# USB-IRIS-W1_INTERFACE.net
KiCad netlist of a schematic drawn in Altium Designer
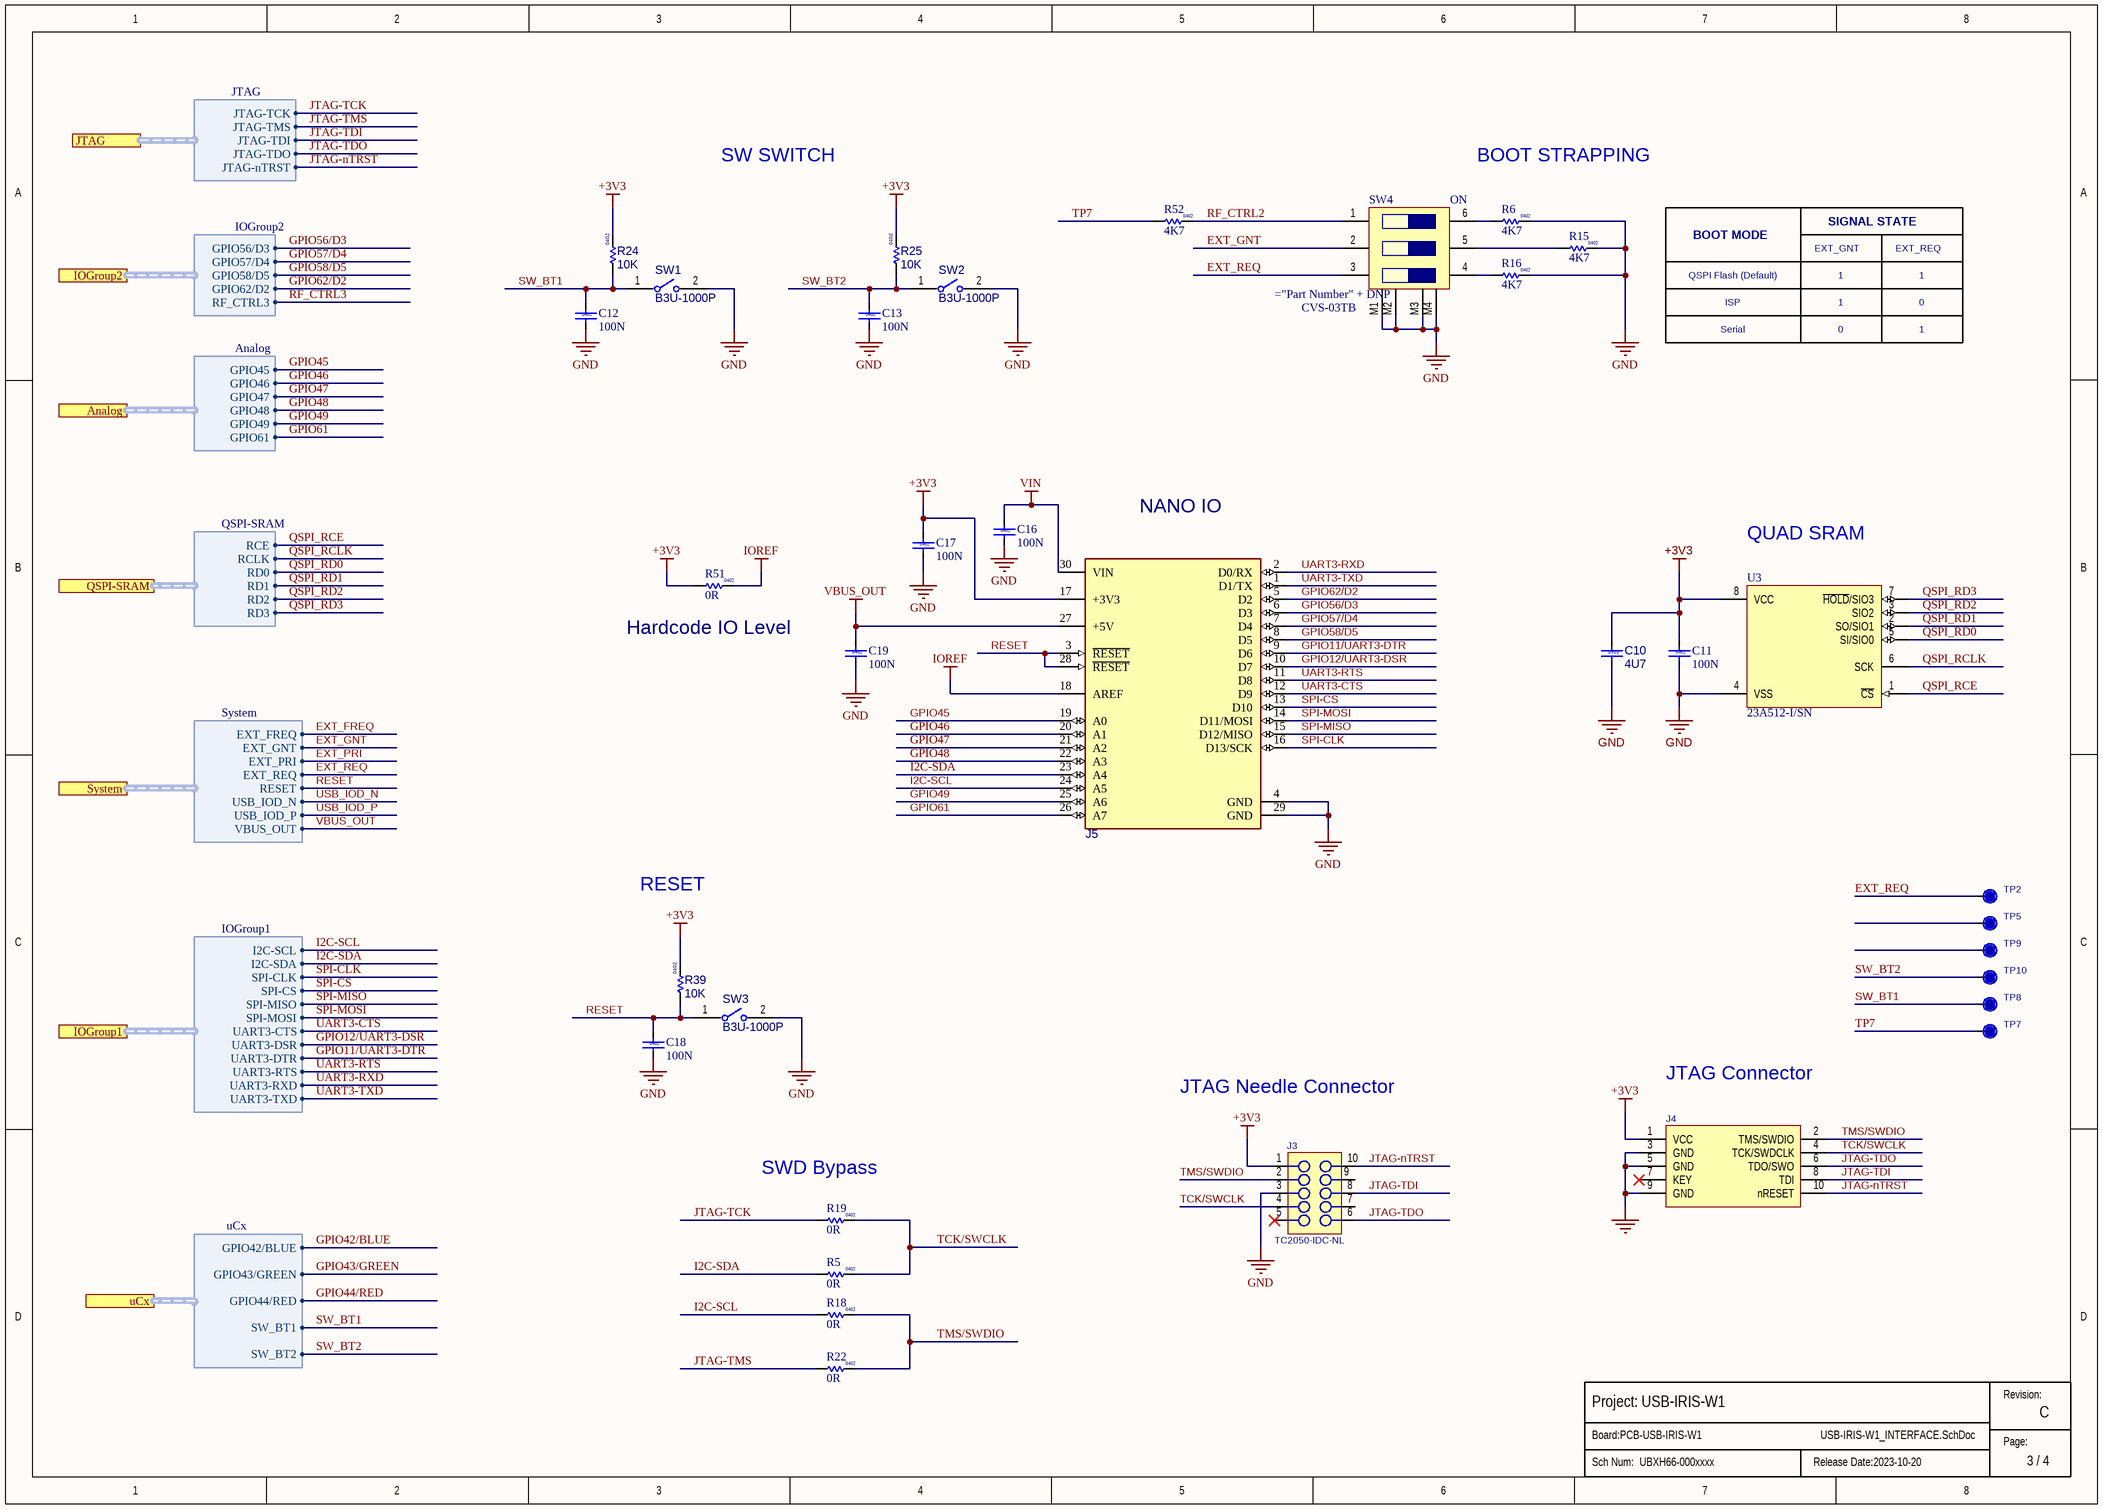
[diagram p0: USB-IRIS-W1_INTERFACE.SchDoc]

(export (version "E")
  (design (tool "Eeschema 10.0.6"))
  (components
    (comp (ref "C10")
      (value "4U7")
      (footprint "Cap 0402 HD")
      (description "CAP CER X5R 0402")
      (fields
        (field (name "SIZE") "0x0y")
        (field (name "PART NUMBER") "UBXH01-0000243")
        (field (name "TOLERANCE") "20%")
        (field (name "EDITOR") "dario.antonaz")
        (field (name "RELEASED BY") "pasquale.scorca")
      )
      (libsource (lib "UBX_Parts_DB_Lib") (part "Cap Chip"))
    )
    (comp (ref "C11")
      (value "100N")
      (footprint "Cap 0402 HD")
      (description "CAP CER X5R 0402 100N 10% 10V")
      (fields
        (field (name "SIZE") "0402")
        (field (name "PART NUMBER") "UBXH01-2021002")
        (field (name "TOLERANCE") "10%")
        (field (name "EDITOR") "roland.rust")
        (field (name "RELEASED BY") "roland.rust")
      )
      (libsource (lib "UBX_Parts_DB_Lib") (part "Cap Chip"))
    )
    (comp (ref "C12")
      (value "100N")
      (footprint "Cap 0402")
      (description "CAP CER X5R 0402 100N 10% 10V")
      (fields
        (field (name "SIZE") "0402")
        (field (name "PART NUMBER") "UBXH01-2021002")
        (field (name "TOLERANCE") "10%")
        (field (name "EDITOR") "roland.rust")
        (field (name "RELEASED BY") "roland.rust")
      )
      (libsource (lib "UBX_Parts_DB_Lib") (part "Cap Chip"))
    )
    (comp (ref "C13")
      (value "100N")
      (footprint "Cap 0402")
      (description "CAP CER X5R 0402 100N 10% 10V")
      (fields
        (field (name "SIZE") "0402")
        (field (name "PART NUMBER") "UBXH01-2021002")
        (field (name "TOLERANCE") "10%")
        (field (name "EDITOR") "roland.rust")
        (field (name "RELEASED BY") "roland.rust")
      )
      (libsource (lib "UBX_Parts_DB_Lib") (part "Cap Chip"))
    )
    (comp (ref "C16")
      (value "100N")
      (footprint "Cap 0402 HD")
      (description "CAP CER X5R 0402 100N 10% 10V")
      (fields
        (field (name "SIZE") "0402")
        (field (name "PART NUMBER") "UBXH01-2021002")
        (field (name "TOLERANCE") "10%")
        (field (name "EDITOR") "roland.rust")
        (field (name "RELEASED BY") "roland.rust")
      )
      (libsource (lib "UBX_Parts_DB_Lib") (part "Cap Chip"))
    )
    (comp (ref "C17")
      (value "100N")
      (footprint "Cap 0402 HD")
      (description "CAP CER X5R 0402 100N 10% 10V")
      (fields
        (field (name "SIZE") "0402")
        (field (name "PART NUMBER") "UBXH01-2021002")
        (field (name "TOLERANCE") "10%")
        (field (name "EDITOR") "roland.rust")
        (field (name "RELEASED BY") "roland.rust")
      )
      (libsource (lib "UBX_Parts_DB_Lib") (part "Cap Chip"))
    )
    (comp (ref "C18")
      (value "100N")
      (footprint "Cap 0402")
      (description "CAP CER X5R 0402 100N 10% 10V")
      (fields
        (field (name "SIZE") "0402")
        (field (name "PART NUMBER") "UBXH01-2021002")
        (field (name "TOLERANCE") "10%")
        (field (name "EDITOR") "roland.rust")
        (field (name "RELEASED BY") "roland.rust")
      )
      (libsource (lib "UBX_Parts_DB_Lib") (part "Cap Chip"))
    )
    (comp (ref "C19")
      (value "100N")
      (footprint "Cap 0402 HD")
      (description "CAP CER X5R 0402 100N 10% 10V")
      (fields
        (field (name "SIZE") "0402")
        (field (name "PART NUMBER") "UBXH01-2021002")
        (field (name "TOLERANCE") "10%")
        (field (name "EDITOR") "roland.rust")
        (field (name "RELEASED BY") "roland.rust")
      )
      (libsource (lib "UBX_Parts_DB_Lib") (part "Cap Chip"))
    )
    (comp (ref "J3")
      (value "TC2050-IDC-NLDNP")
      (footprint "TC2050-IDC-NL")
      (description "CON PADS FOR CBL PLUG-OF-NAILS 10-PIN NO LEGS")
      (fields
        (field (name "MANUFACTURER P/N") "TC2050-IDC-NL")
        (field (name "PART NUMBER") "TC2050-IDC-NL")
        (field (name "MANUFACTURER") "TAG Connect")
        (field (name "ADDED BY") "Paul B")
      )
      (libsource (lib "LEGACY_Rigado_AltiumLib") (part "CON-10Pin_2Row_ALT"))
    )
    (comp (ref "J4")
      (value "130-00099")
      (footprint "HDR.050P-10Pin-2x5-SMT_Key")
      (description "Header 0.05\" 10Pin 2Row SMD Black")
      (fields (field (name "MANUFACTURER") "Samtec"))
      (libsource (lib "Arena_Parts_DB_Lib") (part "JTAG-10Pin"))
    )
    (comp (ref "J5")
      (value "UNK_Arduino")
      (footprint "UNK_Arduino")
      (description "ARDUINO NANO 33 IOT CONN")
      (fields (field (name "PART NUMBER") "UBXH04-0000717") (field (name "EDITOR") "aneeb.sohail"))
      (libsource (lib "UBX_Parts_DB_Lib") (part "UNK_Arduino"))
    )
    (comp (ref "R5")
      (value "0R")
      (footprint "RES_0402_1100Lx600Wx400H_500x600Pad_400G_FLX")
      (description "RES THICK FILM CHIP 0402 0R 0 100mW")
      (fields
        (field (name "SIZE") "0402")
        (field (name "PART NUMBER") "UBXH18-0003002")
        (field (name "TOLERANCE") "0")
        (field (name "EDITOR") "charlotte.biber")
        (field (name "RELEASED BY") "peter.mueller")
      )
      (libsource (lib "UBX_Parts_DB_Lib") (part "Res sm"))
    )
    (comp (ref "R6")
      (value "4K7")
      (footprint "RES_0402_1100Lx600Wx400H_500x600Pad_400G_FLX")
      (description "RES THICK FILM CHIP 0402 4K7 5% 100mW")
      (fields
        (field (name "SIZE") "0402")
        (field (name "PART NUMBER") "UBXH18-0008065")
        (field (name "TOLERANCE") "5%")
        (field (name "EDITOR") "martin.frauchiger")
        (field (name "RELEASED BY") "martin.frauchiger")
      )
      (libsource (lib "UBX_Parts_DB_Lib") (part "Res sm"))
    )
    (comp (ref "R15")
      (value "4K7")
      (footprint "RES_0402_1100Lx600Wx400H_500x600Pad_400G_FLX")
      (description "RES THICK FILM CHIP 0402 4K7 5% 100mW")
      (fields
        (field (name "SIZE") "0402")
        (field (name "PART NUMBER") "UBXH18-0008065")
        (field (name "TOLERANCE") "5%")
        (field (name "EDITOR") "martin.frauchiger")
        (field (name "RELEASED BY") "martin.frauchiger")
      )
      (libsource (lib "UBX_Parts_DB_Lib") (part "Res sm"))
    )
    (comp (ref "R16")
      (value "4K7")
      (footprint "RES_0402_1100Lx600Wx400H_500x600Pad_400G_FLX")
      (description "RES THICK FILM CHIP 0402 4K7 5% 100mW")
      (fields
        (field (name "SIZE") "0402")
        (field (name "PART NUMBER") "UBXH18-0008065")
        (field (name "TOLERANCE") "5%")
        (field (name "EDITOR") "martin.frauchiger")
        (field (name "RELEASED BY") "martin.frauchiger")
      )
      (libsource (lib "UBX_Parts_DB_Lib") (part "Res sm"))
    )
    (comp (ref "R18")
      (value "0R")
      (footprint "RES_0402_1100Lx600Wx400H_500x600Pad_400G_FLX")
      (description "RES THICK FILM CHIP 0402 0R 0 100mW")
      (fields
        (field (name "SIZE") "0402")
        (field (name "PART NUMBER") "UBXH18-0003002")
        (field (name "TOLERANCE") "0")
        (field (name "EDITOR") "charlotte.biber")
        (field (name "RELEASED BY") "peter.mueller")
      )
      (libsource (lib "UBX_Parts_DB_Lib") (part "Res sm"))
    )
    (comp (ref "R19")
      (value "0R")
      (footprint "RES_0402_1100Lx600Wx400H_500x600Pad_400G_FLX")
      (description "RES THICK FILM CHIP 0402 0R 0 100mW")
      (fields
        (field (name "SIZE") "0402")
        (field (name "PART NUMBER") "UBXH18-0003002")
        (field (name "TOLERANCE") "0")
        (field (name "EDITOR") "charlotte.biber")
        (field (name "RELEASED BY") "peter.mueller")
      )
      (libsource (lib "UBX_Parts_DB_Lib") (part "Res sm"))
    )
    (comp (ref "R22")
      (value "0R")
      (footprint "RES_0402_1100Lx600Wx400H_500x600Pad_400G_FLX")
      (description "RES THICK FILM CHIP 0402 0R 0 100mW")
      (fields
        (field (name "SIZE") "0402")
        (field (name "PART NUMBER") "UBXH18-0003002")
        (field (name "TOLERANCE") "0")
        (field (name "EDITOR") "charlotte.biber")
        (field (name "RELEASED BY") "peter.mueller")
      )
      (libsource (lib "UBX_Parts_DB_Lib") (part "Res sm"))
    )
    (comp (ref "R24")
      (value "10K")
      (footprint "RES 0402 HD")
      (description "RES THICK FILM CHIP 0402 10K 5% 100mW")
      (fields
        (field (name "SIZE") "0402")
        (field (name "PART NUMBER") "UBXH18-0008073")
        (field (name "TOLERANCE") "5%")
        (field (name "EDITOR") "martin.frauchiger")
        (field (name "RELEASED BY") "martin.frauchiger")
      )
      (libsource (lib "UBX_Parts_DB_Lib") (part "Res sm"))
    )
    (comp (ref "R25")
      (value "10K")
      (footprint "RES 0402 HD")
      (description "RES THICK FILM CHIP 0402 10K 5% 100mW")
      (fields
        (field (name "SIZE") "0402")
        (field (name "PART NUMBER") "UBXH18-0008073")
        (field (name "TOLERANCE") "5%")
        (field (name "EDITOR") "martin.frauchiger")
        (field (name "RELEASED BY") "martin.frauchiger")
      )
      (libsource (lib "UBX_Parts_DB_Lib") (part "Res sm"))
    )
    (comp (ref "R39")
      (value "10K")
      (footprint "RES 0402 HD")
      (description "RES THICK FILM CHIP 0402 10K 5% 100mW")
      (fields
        (field (name "SIZE") "0402")
        (field (name "PART NUMBER") "UBXH18-0008073")
        (field (name "TOLERANCE") "5%")
        (field (name "EDITOR") "martin.frauchiger")
        (field (name "RELEASED BY") "martin.frauchiger")
      )
      (libsource (lib "UBX_Parts_DB_Lib") (part "Res sm"))
    )
    (comp (ref "R51")
      (value "0R")
      (footprint "RES_0402_1100Lx600Wx400H_500x600Pad_400G_FLX")
      (description "RES THICK FILM CHIP 0402 0R 0 100mW")
      (fields
        (field (name "SIZE") "0402")
        (field (name "PART NUMBER") "UBXH18-0003002")
        (field (name "TOLERANCE") "0")
        (field (name "EDITOR") "charlotte.biber")
        (field (name "RELEASED BY") "peter.mueller")
      )
      (libsource (lib "UBX_Parts_DB_Lib") (part "Res sm"))
    )
    (comp (ref "R52")
      (value "4K7")
      (footprint "RES_0402_1100Lx600Wx400H_500x600Pad_400G_FLX")
      (description "RES THICK FILM CHIP 0402 4K7 5% 100mW")
      (fields
        (field (name "SIZE") "0402")
        (field (name "PART NUMBER") "UBXH18-0008065")
        (field (name "TOLERANCE") "5%")
        (field (name "EDITOR") "martin.frauchiger")
        (field (name "RELEASED BY") "martin.frauchiger")
      )
      (libsource (lib "UBX_Parts_DB_Lib") (part "Res sm"))
    )
    (comp (ref "SW1")
      (value "B3U-1000P")
      (footprint "FP-B3U-1000P-MFG")
      (description "SWITCH TACTILE SPST-NO 0.05A 12V")
      (libsource (lib "Altium Content Vault") (part "ae622034201233ca1abcedc05908f33"))
    )
    (comp (ref "SW2")
      (value "B3U-1000P")
      (footprint "FP-B3U-1000P-MFG")
      (description "SWITCH TACTILE SPST-NO 0.05A 12V")
      (libsource (lib "Altium Content Vault") (part "ae622034201233ca1abcedc05908f33"))
    )
    (comp (ref "SW3")
      (value "B3U-1000P")
      (footprint "FP-B3U-1000P-MFG")
      (description "SWITCH TACTILE SPST-NO 0.05A 12V")
      (libsource (lib "Altium Content Vault") (part "ae622034201233ca1abcedc05908f33"))
    )
    (comp (ref "SW4")
      (value "UBXH19-0000036")
      (footprint "CVS-03")
      (description "Dip Switch SPST 3 Position Surface Mount Slide (Standard) Actuator 100mA 6VDC")
      (fields (field (name "VOLTAGE") "6V") (field (name "MANUFACTURER PART NUMBER 1") "CVS-03TB"))
      (libsource (lib "Schlib1") (part "CVS-03TB"))
    )
    (comp (ref "TP2")
      (value "TP")
      (footprint "TP10R")
      (description "Testpoint, Round 1.0mm Dia")
      (fields
        (field (name "PART NUMBER") "TP10R")
        (field (name "ADDED BY") "Jeremy D")
        (field (name "CHECKED BY") "Paul B")
      )
      (libsource (lib "LEGACY_Rigado_AltiumLib") (part "TP_R"))
    )
    (comp (ref "TP5")
      (value "TP")
      (footprint "TP10R")
      (description "Testpoint, Round 1.0mm Dia")
      (fields
        (field (name "PART NUMBER") "TP10R")
        (field (name "ADDED BY") "Jeremy D")
        (field (name "CHECKED BY") "Paul B")
      )
      (libsource (lib "LEGACY_Rigado_AltiumLib") (part "TP_R"))
    )
    (comp (ref "TP7")
      (value "TP")
      (footprint "TP10R")
      (description "Testpoint, Round 1.0mm Dia")
      (fields
        (field (name "PART NUMBER") "TP10R")
        (field (name "ADDED BY") "Jeremy D")
        (field (name "CHECKED BY") "Paul B")
      )
      (libsource (lib "LEGACY_Rigado_AltiumLib") (part "TP_R"))
    )
    (comp (ref "TP8")
      (value "TP")
      (footprint "TP10R")
      (description "Testpoint, Round 1.0mm Dia")
      (fields
        (field (name "PART NUMBER") "TP10R")
        (field (name "ADDED BY") "Jeremy D")
        (field (name "CHECKED BY") "Paul B")
      )
      (libsource (lib "LEGACY_Rigado_AltiumLib") (part "TP_R"))
    )
    (comp (ref "TP9")
      (value "TP")
      (footprint "TP10R")
      (description "Testpoint, Round 1.0mm Dia")
      (fields
        (field (name "PART NUMBER") "TP10R")
        (field (name "ADDED BY") "Jeremy D")
        (field (name "CHECKED BY") "Paul B")
      )
      (libsource (lib "LEGACY_Rigado_AltiumLib") (part "TP_R"))
    )
    (comp (ref "TP10")
      (value "TP")
      (footprint "TP10R")
      (description "Testpoint, Round 1.0mm Dia")
      (fields
        (field (name "PART NUMBER") "TP10R")
        (field (name "ADDED BY") "Jeremy D")
        (field (name "CHECKED BY") "Paul B")
      )
      (libsource (lib "LEGACY_Rigado_AltiumLib") (part "TP_R"))
    )
    (comp (ref "U3")
      (value "23A512-I/SN")
      (footprint "SOIC127P599X173-8N")
      (description "IC SRAM 512KBIT SPI/QUAD 8SOIC")
      (fields (field (name "MANUFACTURER") "Microchip Technology"))
      (libsource (lib "Schlib1") (part "23A512-I/SN"))
    )
  )
  (nets
    (net (code "8") (name "+3V3") (class "Default")
      (node (ref "C10") (pin "1") (pinfunction "1_1") (pintype "passive"))
      (node (ref "C11") (pin "1") (pinfunction "1_1") (pintype "passive"))
      (node (ref "C17") (pin "1") (pinfunction "1_1") (pintype "passive"))
      (node (ref "J3") (pin "1") (pintype "passive"))
      (node (ref "J4") (pin "1") (pinfunction "VCC_1") (pintype "passive"))
      (node (ref "J5") (pin "17") (pinfunction "+3V3_17") (pintype "power_in"))
      (node (ref "R24") (pin "2") (pinfunction "2_2") (pintype "passive"))
      (node (ref "R25") (pin "2") (pinfunction "2_2") (pintype "passive"))
      (node (ref "R39") (pin "2") (pinfunction "2_2") (pintype "passive"))
      (node (ref "R51") (pin "1") (pinfunction "1_1") (pintype "passive"))
      (node (ref "U3") (pin "8") (pinfunction "VCC_8") (pintype "power_in"))
    )
    (net (code "10") (name "/EXT_GNT") (class "Default") (node (ref "SW4") (pin "2") (pintype "passive")))
    (net (code "12") (name "/EXT_REQ") (class "Default")
      (node (ref "SW4") (pin "3") (pintype "passive"))
      (node (ref "TP2") (pin "1") (pintype "passive"))
    )
    (net (code "13") (name "/GPIO11{slash}UART3-DTR") (class "Default")
      (node (ref "J5") (pin "9") (pinfunction "D6_9") (pintype "bidirectional"))
    )
    (net (code "14") (name "/GPIO12{slash}UART3-DSR") (class "Default")
      (node (ref "J5") (pin "10") (pinfunction "D7_10") (pintype "bidirectional"))
    )
    (net (code "18") (name "/GPIO45") (class "Default")
      (node (ref "J5") (pin "19") (pinfunction "A0_19") (pintype "bidirectional"))
    )
    (net (code "19") (name "/GPIO46") (class "Default")
      (node (ref "J5") (pin "20") (pinfunction "A1_20") (pintype "bidirectional"))
    )
    (net (code "20") (name "/GPIO47") (class "Default")
      (node (ref "J5") (pin "21") (pinfunction "A2_21") (pintype "bidirectional"))
    )
    (net (code "21") (name "/GPIO48") (class "Default")
      (node (ref "J5") (pin "22") (pinfunction "A3_22") (pintype "bidirectional"))
    )
    (net (code "22") (name "/GPIO49") (class "Default")
      (node (ref "J5") (pin "25") (pinfunction "A6_25") (pintype "bidirectional"))
    )
    (net (code "23") (name "/GPIO56{slash}D3") (class "Default")
      (node (ref "J5") (pin "6") (pinfunction "D3_6") (pintype "bidirectional"))
    )
    (net (code "24") (name "/GPIO57{slash}D4") (class "Default")
      (node (ref "J5") (pin "7") (pinfunction "D4_7") (pintype "bidirectional"))
    )
    (net (code "25") (name "/GPIO58{slash}D5") (class "Default")
      (node (ref "J5") (pin "8") (pinfunction "D5_8") (pintype "bidirectional"))
    )
    (net (code "26") (name "/GPIO61") (class "Default")
      (node (ref "J5") (pin "26") (pinfunction "A7_26") (pintype "bidirectional"))
    )
    (net (code "27") (name "/GPIO62{slash}D2") (class "Default")
      (node (ref "J5") (pin "5") (pinfunction "D2_5") (pintype "bidirectional"))
    )
    (net (code "28") (name "/I2C-SCL") (class "Default")
      (node (ref "J5") (pin "24") (pinfunction "A5_24") (pintype "bidirectional"))
      (node (ref "R18") (pin "1") (pinfunction "1_1") (pintype "passive"))
    )
    (net (code "29") (name "/I2C-SDA") (class "Default")
      (node (ref "J5") (pin "23") (pinfunction "A4_23") (pintype "bidirectional"))
      (node (ref "R5") (pin "1") (pinfunction "1_1") (pintype "passive"))
    )
    (net (code "30") (name "/JTAG-TCK") (class "Default")
      (node (ref "R19") (pin "1") (pinfunction "1_1") (pintype "passive"))
    )
    (net (code "31") (name "/JTAG-TDI") (class "Default")
      (node (ref "J3") (pin "8") (pintype "passive"))
      (node (ref "J4") (pin "8") (pinfunction "TDI_8") (pintype "passive"))
    )
    (net (code "32") (name "/JTAG-TDO") (class "Default")
      (node (ref "J3") (pin "6") (pintype "passive"))
      (node (ref "J4") (pin "6") (pinfunction "TDO/SWO_6") (pintype "passive"))
    )
    (net (code "33") (name "/JTAG-TMS") (class "Default")
      (node (ref "R22") (pin "1") (pinfunction "1_1") (pintype "passive"))
    )
    (net (code "34") (name "/JTAG-nTRST") (class "Default")
      (node (ref "J3") (pin "10") (pintype "passive"))
      (node (ref "J4") (pin "10") (pinfunction "nRESET_10") (pintype "passive"))
    )
    (net (code "35") (name "/QSPI_RCE") (class "Default")
      (node (ref "U3") (pin "1") (pinfunction "~{CS}_1") (pintype "input"))
    )
    (net (code "36") (name "/QSPI_RCLK") (class "Default")
      (node (ref "U3") (pin "6") (pinfunction "SCK_6") (pintype "passive"))
    )
    (net (code "37") (name "/QSPI_RD0") (class "Default")
      (node (ref "U3") (pin "5") (pinfunction "SI/SIO0_5") (pintype "bidirectional"))
    )
    (net (code "38") (name "/QSPI_RD1") (class "Default")
      (node (ref "U3") (pin "2") (pinfunction "SO/SIO1_2") (pintype "bidirectional"))
    )
    (net (code "39") (name "/QSPI_RD2") (class "Default")
      (node (ref "U3") (pin "3") (pinfunction "SIO2_3") (pintype "bidirectional"))
    )
    (net (code "40") (name "/QSPI_RD3") (class "Default")
      (node (ref "U3") (pin "7") (pinfunction "~{HOLD}/SIO3_7") (pintype "bidirectional"))
    )
    (net (code "41") (name "/RESET") (class "Default")
      (node (ref "C18") (pin "1") (pinfunction "1_1") (pintype "passive"))
      (node (ref "J5") (pin "28") (pinfunction "~{RESET}_28") (pintype "input"))
      (node (ref "J5") (pin "3") (pinfunction "~{RESET}_3") (pintype "input"))
      (node (ref "R39") (pin "1") (pinfunction "1_1") (pintype "passive"))
      (node (ref "SW3") (pin "1") (pinfunction "1_1") (pintype "passive"))
    )
    (net (code "42") (name "/RF_CTRL2") (class "Default")
      (node (ref "R52") (pin "2") (pinfunction "2_2") (pintype "passive"))
      (node (ref "SW4") (pin "1") (pintype "passive"))
    )
    (net (code "44") (name "/SPI-CLK") (class "Default")
      (node (ref "J5") (pin "16") (pinfunction "D13/SCK_16") (pintype "bidirectional"))
    )
    (net (code "45") (name "/SPI-CS") (class "Default")
      (node (ref "J5") (pin "13") (pinfunction "D10_13") (pintype "bidirectional"))
    )
    (net (code "46") (name "/SPI-MISO") (class "Default")
      (node (ref "J5") (pin "15") (pinfunction "D12/MISO_15") (pintype "bidirectional"))
    )
    (net (code "47") (name "/SPI-MOSI") (class "Default")
      (node (ref "J5") (pin "14") (pinfunction "D11/MOSI_14") (pintype "bidirectional"))
    )
    (net (code "48") (name "/SW_BT1") (class "Default")
      (node (ref "C12") (pin "1") (pinfunction "1_1") (pintype "passive"))
      (node (ref "R24") (pin "1") (pinfunction "1_1") (pintype "passive"))
      (node (ref "SW1") (pin "1") (pinfunction "1_1") (pintype "passive"))
      (node (ref "TP8") (pin "1") (pintype "passive"))
    )
    (net (code "49") (name "/SW_BT2") (class "Default")
      (node (ref "C13") (pin "1") (pinfunction "1_1") (pintype "passive"))
      (node (ref "R25") (pin "1") (pinfunction "1_1") (pintype "passive"))
      (node (ref "SW2") (pin "1") (pinfunction "1_1") (pintype "passive"))
      (node (ref "TP10") (pin "1") (pintype "passive"))
    )
    (net (code "50") (name "/TCK{slash}SWCLK") (class "Default")
      (node (ref "J3") (pin "4") (pintype "passive"))
      (node (ref "J4") (pin "4") (pinfunction "TCK/SWDCLK_4") (pintype "passive"))
      (node (ref "R19") (pin "2") (pinfunction "2_2") (pintype "passive"))
      (node (ref "R5") (pin "2") (pinfunction "2_2") (pintype "passive"))
    )
    (net (code "51") (name "/TMS{slash}SWDIO") (class "Default")
      (node (ref "J3") (pin "2") (pintype "passive"))
      (node (ref "J4") (pin "2") (pinfunction "TMS/SWDIO_2") (pintype "passive"))
      (node (ref "R18") (pin "2") (pinfunction "2_2") (pintype "passive"))
      (node (ref "R22") (pin "2") (pinfunction "2_2") (pintype "passive"))
    )
    (net (code "52") (name "/TP7") (class "Default")
      (node (ref "R52") (pin "1") (pinfunction "1_1") (pintype "passive"))
      (node (ref "TP7") (pin "1") (pintype "passive"))
    )
    (net (code "53") (name "/UART3-CTS") (class "Default")
      (node (ref "J5") (pin "12") (pinfunction "D9_12") (pintype "bidirectional"))
    )
    (net (code "54") (name "/UART3-RTS") (class "Default")
      (node (ref "J5") (pin "11") (pinfunction "D8_11") (pintype "bidirectional"))
    )
    (net (code "55") (name "/UART3-RXD") (class "Default")
      (node (ref "J5") (pin "2") (pinfunction "D0/RX_2") (pintype "bidirectional"))
    )
    (net (code "56") (name "/UART3-TXD") (class "Default")
      (node (ref "J5") (pin "1") (pinfunction "D1/TX_1") (pintype "bidirectional"))
    )
    (net (code "66") (name "GND") (class "Default")
      (node (ref "C10") (pin "2") (pinfunction "2_2") (pintype "passive"))
      (node (ref "C11") (pin "2") (pinfunction "2_2") (pintype "passive"))
      (node (ref "C12") (pin "2") (pinfunction "2_2") (pintype "passive"))
      (node (ref "C13") (pin "2") (pinfunction "2_2") (pintype "passive"))
      (node (ref "C16") (pin "2") (pinfunction "2_2") (pintype "passive"))
      (node (ref "C17") (pin "2") (pinfunction "2_2") (pintype "passive"))
      (node (ref "C18") (pin "2") (pinfunction "2_2") (pintype "passive"))
      (node (ref "C19") (pin "2") (pinfunction "2_2") (pintype "passive"))
      (node (ref "J3") (pin "3") (pintype "passive"))
      (node (ref "J4") (pin "3") (pinfunction "GND_3") (pintype "passive"))
      (node (ref "J4") (pin "5") (pinfunction "GND_5") (pintype "passive"))
      (node (ref "J4") (pin "9") (pinfunction "GND_9") (pintype "passive"))
      (node (ref "J5") (pin "29") (pinfunction "GND_29") (pintype "power_in"))
      (node (ref "J5") (pin "4") (pinfunction "GND_4") (pintype "power_in"))
      (node (ref "R15") (pin "2") (pinfunction "2_2") (pintype "passive"))
      (node (ref "R16") (pin "2") (pinfunction "2_2") (pintype "passive"))
      (node (ref "R6") (pin "2") (pinfunction "2_2") (pintype "passive"))
      (node (ref "SW1") (pin "2") (pinfunction "2_2") (pintype "passive"))
      (node (ref "SW2") (pin "2") (pinfunction "2_2") (pintype "passive"))
      (node (ref "SW3") (pin "2") (pinfunction "2_2") (pintype "passive"))
      (node (ref "SW4") (pin "M1") (pintype "passive"))
      (node (ref "SW4") (pin "M2") (pintype "passive"))
      (node (ref "SW4") (pin "M3") (pintype "passive"))
      (node (ref "SW4") (pin "M4") (pintype "passive"))
      (node (ref "U3") (pin "4") (pinfunction "VSS_4") (pintype "power_in"))
    )
    (net (code "67") (name "IOREF") (class "Default")
      (node (ref "J5") (pin "18") (pinfunction "AREF_18") (pintype "passive"))
      (node (ref "R51") (pin "2") (pinfunction "2_2") (pintype "passive"))
    )
    (net (code "68") (name "Net-(R6-Pad1)") (class "Default")
      (node (ref "R6") (pin "1") (pinfunction "1_1") (pintype "passive"))
      (node (ref "SW4") (pin "6") (pintype "passive"))
    )
    (net (code "69") (name "Net-(R15-Pad1)") (class "Default")
      (node (ref "R15") (pin "1") (pinfunction "1_1") (pintype "passive"))
      (node (ref "SW4") (pin "5") (pintype "passive"))
    )
    (net (code "70") (name "Net-(R16-Pad1)") (class "Default")
      (node (ref "R16") (pin "1") (pinfunction "1_1") (pintype "passive"))
      (node (ref "SW4") (pin "4") (pintype "passive"))
    )
    (net (code "71") (name "VBUS_OUT") (class "Default")
      (node (ref "C19") (pin "1") (pinfunction "1_1") (pintype "passive"))
      (node (ref "J5") (pin "27") (pinfunction "+5V_27") (pintype "power_in"))
    )
    (net (code "72") (name "VIN") (class "Default")
      (node (ref "C16") (pin "1") (pinfunction "1_1") (pintype "passive"))
      (node (ref "J5") (pin "30") (pinfunction "VIN_30") (pintype "power_in"))
    )
    (net (code "73") (name "unconnected-(J3-Pad5)") (class "Default")
      (node (ref "J3") (pin "5") (pintype "passive+no_connect"))
    )
    (net (code "74") (name "unconnected-(J3-Pad7)") (class "Default")
      (node (ref "J3") (pin "7") (pintype "passive"))
    )
    (net (code "75") (name "unconnected-(J3-Pad9)") (class "Default")
      (node (ref "J3") (pin "9") (pintype "passive"))
    )
    (net (code "76") (name "unconnected-(J4-KEY-Pad7)") (class "Default")
      (node (ref "J4") (pin "7") (pinfunction "KEY_7") (pintype "passive+no_connect"))
    )
    (net (code "77") (name "unconnected-(TP5-Pad1)") (class "Default")
      (node (ref "TP5") (pin "1") (pintype "passive"))
    )
    (net (code "78") (name "unconnected-(TP9-Pad1)") (class "Default")
      (node (ref "TP9") (pin "1") (pintype "passive"))
    )
  )
)
